# bc95.net
KiCad netlist of a schematic drawn in Altium Designer
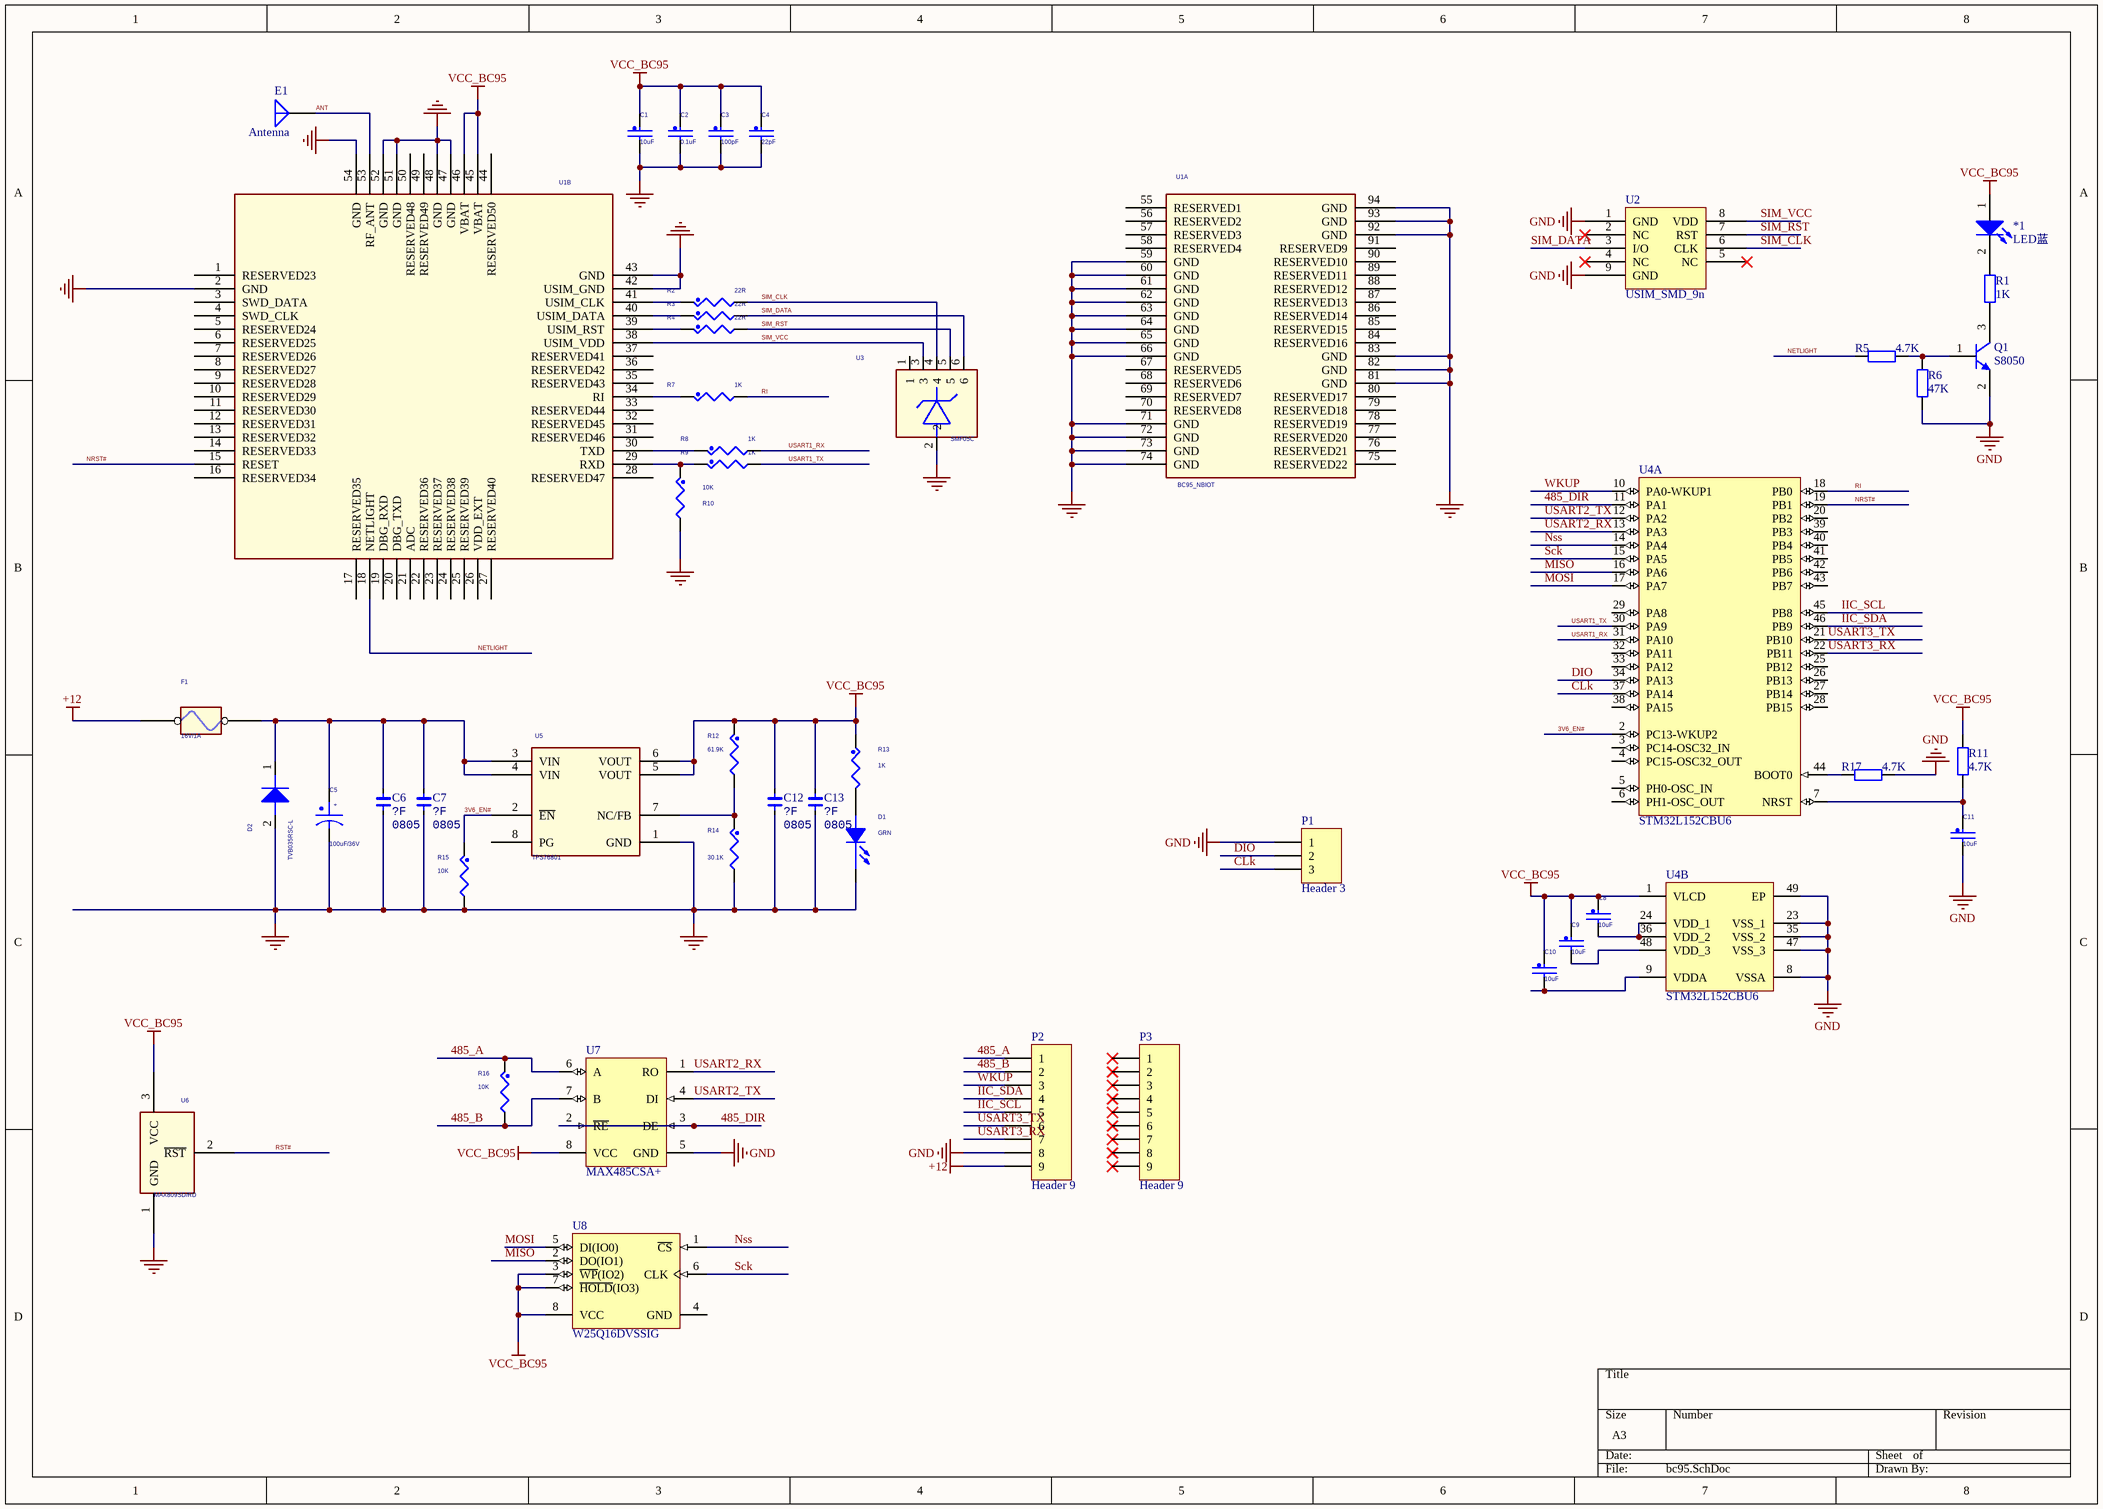
[diagram p0: bc95.SchDoc]

(export (version "E")
  (design (tool "Eeschema 10.0.6"))
  (components
    (comp (ref "*1") (value "LED蓝") (footprint "LED_0603_BLUE") (libsource (lib "du") (part "LED蓝")))
    (comp (ref "C1")
      (value "10uF")
      (footprint "CAP_0603")
      (description "CAP 22uF 1210 25V 10%")
      (fields (field (name "MFG") "Murata") (field (name "MPN") "GRM-RC1210-227K"))
      (libsource (lib "*") (part "CAP_NP"))
    )
    (comp (ref "C2")
      (value "0.1uF")
      (footprint "CAP_0603")
      (description "CAP  0.1uF 0402 25V 10%")
      (fields (field (name "PART NUMBER") "132-000**") (field (name "VOLTAGE") "25V"))
      (libsource (lib "*") (part "CAP_NP"))
    )
    (comp (ref "C3")
      (value "100pF")
      (footprint "CAP_0603")
      (description "CAP  0.1uF 0402 25V 10%")
      (fields (field (name "TOLERANCE") "10%") (field (name "MPN") "GRM-RC0402-104K"))
      (libsource (lib "*") (part "CAP_NP"))
    )
    (comp (ref "C4")
      (value "22pF")
      (footprint "CAP_0603")
      (description "CAP  0.1uF 0402 25V 10%")
      (fields (field (name "PART NUMBER") "132-000**") (field (name "VOLTAGE") "25V"))
      (libsource (lib "*") (part "CAP_NP"))
    )
    (comp (ref "C5")
      (value "100uF/36V")
      (footprint "CAP_TAN_D2917")
      (description "CAP 220UF 1010mm 35V 10%")
      (fields (field (name "MFG") "Murata") (field (name "MPN") "C1210C476K8PAC"))
      (libsource (lib "*") (part "CAP_POL"))
    )
    (comp (ref "C6")
      (value "?F")
      (footprint "PCB_PassiveCap:CAP_0805")
      (description "Capacitor")
      (fields (field (name "TYPE") "0805"))
      (libsource (lib "SCH_Passive") (part "Cap_0805"))
    )
    (comp (ref "C7")
      (value "?F")
      (footprint "PCB_PassiveCap:CAP_0805")
      (description "Capacitor")
      (fields (field (name "TYPE") "0805"))
      (libsource (lib "SCH_Passive") (part "Cap_0805"))
    )
    (comp (ref "C8")
      (value "10uF")
      (footprint "CAP_0603")
      (description "CAP 22uF 1210 25V 10%")
      (fields (field (name "MFG") "Murata") (field (name "MPN") "GRM-RC1210-227K"))
      (libsource (lib "*") (part "CAP_NP"))
    )
    (comp (ref "C9")
      (value "10uF")
      (footprint "CAP_0603")
      (description "CAP 22uF 1210 25V 10%")
      (fields (field (name "MFG") "Murata") (field (name "MPN") "GRM-RC1210-227K"))
      (libsource (lib "*") (part "CAP_NP"))
    )
    (comp (ref "C10")
      (value "10uF")
      (footprint "CAP_0603")
      (description "CAP 22uF 1210 25V 10%")
      (fields (field (name "MFG") "Murata") (field (name "MPN") "GRM-RC1210-227K"))
      (libsource (lib "*") (part "CAP_NP"))
    )
    (comp (ref "C11")
      (value "10uF")
      (footprint "CAP_0603")
      (description "CAP 22uF 1210 25V 10%")
      (fields (field (name "MFG") "Murata") (field (name "MPN") "GRM-RC1210-227K"))
      (libsource (lib "*") (part "CAP_NP"))
    )
    (comp (ref "C12")
      (value "?F")
      (footprint "PCB_PassiveCap:CAP_0805")
      (description "Capacitor")
      (fields (field (name "TYPE") "0805"))
      (libsource (lib "SCH_Passive") (part "Cap_0805"))
    )
    (comp (ref "C13")
      (value "?F")
      (footprint "PCB_PassiveCap:CAP_0805")
      (description "Capacitor")
      (fields (field (name "TYPE") "0805"))
      (libsource (lib "SCH_Passive") (part "Cap_0805"))
    )
    (comp (ref "D1") (value "GRN") (footprint "LED_0603_GREEN") (libsource (lib "*") (part "F5F1")))
    (comp (ref "D2")
      (value "TVB035RSC-L")
      (footprint "IND_1008")
      (description "二极管 浪涌保 dm=35V,Ih=150mA DO-214AA SMB")
      (fields (field (name "MFG") "TYCO"))
      (libsource (lib "*") (part "DIODE"))
    )
    (comp (ref "E1")
      (value "Antenna")
      (footprint "IPX")
      (description "Generic Antenna")
      (fields (field (name "PUBLISHER") "Altium Limited"))
      (libsource (lib "Miscellaneous Devices") (part "Antenna"))
    )
    (comp (ref "F1") (value "16V/1A") (footprint "RES_0805") (libsource (lib "*") (part "FUSEHOLDER")))
    (comp (ref "P1")
      (value "Header 3")
      (footprint "HDR1X3")
      (description "Header, 3-Pin")
      (fields (field (name "PUBLISHER") "Altium Limited"))
      (libsource (lib "Miscellaneous Connectors") (part "Header 3"))
    )
    (comp (ref "P2")
      (value "Header 9")
      (footprint "HDR1X9")
      (description "Header, 9-Pin")
      (fields (field (name "PUBLISHER") "Altium Limited"))
      (libsource (lib "Miscellaneous Connectors") (part "Header 9"))
    )
    (comp (ref "P3")
      (value "Header 9")
      (footprint "HDR1X9")
      (description "Header, 9-Pin")
      (fields (field (name "PUBLISHER") "Altium Limited"))
      (libsource (lib "Miscellaneous Connectors") (part "Header 9"))
    )
    (comp (ref "Q1")
      (value "S8050")
      (footprint "SOT23_M")
      (description "NPN Bipolar Transistor")
      (fields (field (name "PUBLISHER") "Altium Limited"))
      (libsource (lib "Sch_Lib_CommonDrivice") (part "QNPN"))
    )
    (comp (ref "R1")
      (value "1K")
      (footprint "RES_0603")
      (description "Resistor")
      (fields (field (name "PUBLISHER") "Altium Limited"))
      (libsource (lib "") (part "Res_2"))
    )
    (comp (ref "R2")
      (value "22R")
      (footprint "RES_0603")
      (fields
        (field (name "TOLERANCE") "5%")
        (field (name "MFG") "Yageo")
        (field (name "MPN") "RC1206JR-07330R")
      )
      (libsource (lib "*") (part "RES"))
    )
    (comp (ref "R3")
      (value "22R")
      (footprint "RES_0603")
      (fields
        (field (name "MPN") "RC1206JR-07330R")
        (field (name "MFG") "Yageo")
        (field (name "TOLERANCE") "5%")
      )
      (libsource (lib "*") (part "RES"))
    )
    (comp (ref "R4")
      (value "22R")
      (footprint "RES_0603")
      (fields
        (field (name "MPN") "RC1206JR-07330R")
        (field (name "MFG") "Yageo")
        (field (name "TOLERANCE") "5%")
      )
      (libsource (lib "*") (part "RES"))
    )
    (comp (ref "R5")
      (value "4.7K")
      (footprint "RES_0603")
      (description "Resistor")
      (fields (field (name "PUBLISHER") "Altium Limited"))
      (libsource (lib "") (part "Res_1"))
    )
    (comp (ref "R6")
      (value "47K")
      (footprint "RES_0603")
      (description "Resistor")
      (fields (field (name "PUBLISHER") "Altium Limited"))
      (libsource (lib "Sch_Lib_CommonDrivice") (part "Res"))
    )
    (comp (ref "R7")
      (value "1K")
      (footprint "RES_0603")
      (fields
        (field (name "TOLERANCE") "5%")
        (field (name "MFG") "Yageo")
        (field (name "MPN") "RC1206JR-07330R")
      )
      (libsource (lib "*") (part "RES"))
    )
    (comp (ref "R8")
      (value "1K")
      (footprint "RES_0603")
      (fields
        (field (name "MPN") "RC1206JR-07330R")
        (field (name "MFG") "Yageo")
        (field (name "TOLERANCE") "5%")
      )
      (libsource (lib "*") (part "RES"))
    )
    (comp (ref "R9")
      (value "1K")
      (footprint "RES_0603")
      (fields
        (field (name "MPN") "RC1206JR-07330R")
        (field (name "MFG") "Yageo")
        (field (name "TOLERANCE") "5%")
      )
      (libsource (lib "*") (part "RES"))
    )
    (comp (ref "R10")
      (value "10K")
      (footprint "RES_0603")
      (fields
        (field (name "MPN") "RC1206JR-07330R")
        (field (name "MFG") "Yageo")
        (field (name "TOLERANCE") "5%")
      )
      (libsource (lib "*") (part "RES"))
    )
    (comp (ref "R11")
      (value "4.7K")
      (footprint "RES_0603")
      (description "Resistor")
      (fields (field (name "PUBLISHER") "Altium Limited"))
      (libsource (lib "Sch_Lib_CommonDrivice") (part "Res"))
    )
    (comp (ref "R12")
      (value "61.9K")
      (footprint "RES_0603")
      (fields
        (field (name "TOLERANCE") "5%")
        (field (name "MFG") "Yageo")
        (field (name "MPN") "RC1206JR-07330R")
      )
      (libsource (lib "*") (part "RES"))
    )
    (comp (ref "R13")
      (value "1K")
      (footprint "RES_0603")
      (fields (field (name "TOLERANCE") "5%") (field (name "MPN") "RC0402JR-07330R"))
      (libsource (lib "*") (part "RES"))
    )
    (comp (ref "R14")
      (value "30.1K")
      (footprint "RES_0603")
      (fields
        (field (name "MPN") "RC1206JR-07330R")
        (field (name "MFG") "Yageo")
        (field (name "TOLERANCE") "5%")
      )
      (libsource (lib "*") (part "RES"))
    )
    (comp (ref "R15")
      (value "10K")
      (footprint "RES_0603")
      (fields
        (field (name "MPN") "RC1206JR-07330R")
        (field (name "MFG") "Yageo")
        (field (name "TOLERANCE") "5%")
      )
      (libsource (lib "*") (part "RES"))
    )
    (comp (ref "R16")
      (value "10K")
      (footprint "RES_0603")
      (fields
        (field (name "MPN") "RC1206JR-07330R")
        (field (name "MFG") "Yageo")
        (field (name "TOLERANCE") "5%")
      )
      (libsource (lib "*") (part "RES"))
    )
    (comp (ref "R17")
      (value "4.7K")
      (footprint "RES_0603")
      (description "Resistor")
      (fields (field (name "PUBLISHER") "Altium Limited"))
      (libsource (lib "") (part "Res_1"))
    )
    (comp (ref "U1") (value "BC95_NBIOT") (footprint "BC95") (libsource (lib "*") (part "BC95_NBIOT_4")))
    (comp (ref "U2")
      (value "USIM_SMD_9n")
      (footprint "SON127P600X75_HS-9N")
      (libsource (lib "du") (part "USIM_SMD_9n"))
    )
    (comp (ref "U3") (value "SMF05C") (footprint "SOT65P210X100-6N") (libsource (lib "*") (part "SMF05C_0")))
    (comp (ref "U4")
      (value "STM32L152CBU6")
      (footprint "STM-UFQFPN48_M")
      (libsource (lib "Altium Content Vault") (part "MC-ARM-STM32L15XX6_8_B-SQ49"))
    )
    (comp (ref "U5") (value "TPS76801") (footprint "SO8_M") (libsource (lib "*") (part "TPS768XX_1")))
    (comp (ref "U6") (value "MAX809SD/RD") (footprint "SOT23_M") (libsource (lib "*") (part "MAX809SD/RD")))
    (comp (ref "U7")
      (value "MAX485CSA+")
      (footprint "MAXM-MAX485CSA+-8_M")
      (fields (field (name "MANUFACTURER") "Maxim"))
      (libsource (lib "Altium Content Vault") (part "MAXM-MAX485CSA+-8"))
    )
    (comp (ref "U8")
      (value "W25Q16DVSSIG")
      (footprint "WINB-W25Q16DVSSIG-8_M")
      (description "IC FLASH 16MBIT 104MHZ 8SOIC")
      (fields (field (name "MANUFACTURER") "Winbond"))
      (libsource (lib "Altium Content Vault") (part "WINB-W25Q16DVSSIG-8"))
    )
  )
  (nets
    (net (code "1") (name "+12") (class "Default")
      (node (ref "F1") (pin "1") (pinfunction "1_1") (pintype "passive"))
      (node (ref "P2") (pin "9") (pinfunction "9_9") (pintype "passive"))
    )
    (net (code "2") (name "/3V6_EN#") (class "Default")
      (node (ref "R15") (pin "1") (pinfunction "1_1") (pintype "passive"))
      (node (ref "U4") (pin "2") (pinfunction "PC13-WKUP2_2") (pintype "bidirectional"))
      (node (ref "U5") (pin "2") (pinfunction "~{EN}_2") (pintype "passive"))
    )
    (net (code "3") (name "/485_A") (class "Default")
      (node (ref "P2") (pin "1") (pinfunction "1_1") (pintype "passive"))
      (node (ref "R16") (pin "1") (pinfunction "1_1") (pintype "passive"))
      (node (ref "U7") (pin "6") (pinfunction "A_6") (pintype "bidirectional"))
    )
    (net (code "4") (name "/485_B") (class "Default")
      (node (ref "P2") (pin "2") (pinfunction "2_2") (pintype "passive"))
      (node (ref "R16") (pin "2") (pinfunction "2_2") (pintype "passive"))
      (node (ref "U7") (pin "7") (pinfunction "B_7") (pintype "bidirectional"))
    )
    (net (code "5") (name "/485_DIR") (class "Default")
      (node (ref "U4") (pin "11") (pinfunction "PA1_11") (pintype "bidirectional"))
      (node (ref "U7") (pin "2") (pinfunction "~{RE}_2") (pintype "input"))
      (node (ref "U7") (pin "3") (pinfunction "DE_3") (pintype "input"))
    )
    (net (code "6") (name "/ANT") (class "Default")
      (node (ref "E1") (pin "1") (pinfunction "A_1") (pintype "passive"))
      (node (ref "U1") (pin "53") (pinfunction "RF_ANT_53") (pintype "passive"))
    )
    (net (code "7") (name "/CLk") (class "Default")
      (node (ref "P1") (pin "3") (pinfunction "3_3") (pintype "passive"))
      (node (ref "U4") (pin "37") (pinfunction "PA14_37") (pintype "bidirectional"))
    )
    (net (code "8") (name "/DIO") (class "Default")
      (node (ref "P1") (pin "2") (pinfunction "2_2") (pintype "passive"))
      (node (ref "U4") (pin "34") (pinfunction "PA13_34") (pintype "bidirectional"))
    )
    (net (code "9") (name "/IIC_SCL") (class "Default")
      (node (ref "P2") (pin "5") (pinfunction "5_5") (pintype "passive"))
      (node (ref "U4") (pin "45") (pinfunction "PB8_45") (pintype "bidirectional"))
    )
    (net (code "10") (name "/IIC_SDA") (class "Default")
      (node (ref "P2") (pin "4") (pinfunction "4_4") (pintype "passive"))
      (node (ref "U4") (pin "46") (pinfunction "PB9_46") (pintype "bidirectional"))
    )
    (net (code "11") (name "/MISO") (class "Default")
      (node (ref "U4") (pin "16") (pinfunction "PA6_16") (pintype "bidirectional"))
      (node (ref "U8") (pin "2") (pinfunction "DO(IO1)_2") (pintype "bidirectional"))
    )
    (net (code "12") (name "/MOSI") (class "Default")
      (node (ref "U4") (pin "17") (pinfunction "PA7_17") (pintype "bidirectional"))
      (node (ref "U8") (pin "5") (pinfunction "DI(IO0)_5") (pintype "bidirectional"))
    )
    (net (code "13") (name "/NETLIGHT") (class "Default")
      (node (ref "R5") (pin "2") (pinfunction "2_2") (pintype "passive"))
      (node (ref "U1") (pin "18") (pinfunction "NETLIGHT_18") (pintype "passive"))
    )
    (net (code "14") (name "/NRST#") (class "Default")
      (node (ref "U1") (pin "15") (pinfunction "RESET_15") (pintype "passive"))
      (node (ref "U4") (pin "19") (pinfunction "PB1_19") (pintype "bidirectional"))
    )
    (net (code "15") (name "/Nss") (class "Default")
      (node (ref "U4") (pin "14") (pinfunction "PA4_14") (pintype "bidirectional"))
      (node (ref "U8") (pin "1") (pinfunction "~{CS}_1") (pintype "input"))
    )
    (net (code "16") (name "/RI") (class "Default")
      (node (ref "R7") (pin "2") (pinfunction "2_2") (pintype "passive"))
      (node (ref "U4") (pin "18") (pinfunction "PB0_18") (pintype "bidirectional"))
    )
    (net (code "17") (name "/RST#") (class "Default")
      (node (ref "U6") (pin "2") (pinfunction "~{RST}_2") (pintype "passive"))
    )
    (net (code "18") (name "/SIM_CLK") (class "Default")
      (node (ref "R2") (pin "2") (pinfunction "2_2") (pintype "passive"))
      (node (ref "U2") (pin "6") (pinfunction "CLK_6") (pintype "passive"))
      (node (ref "U3") (pin "4") (pinfunction "4_4") (pintype "passive"))
    )
    (net (code "19") (name "/SIM_DATA") (class "Default")
      (node (ref "R3") (pin "2") (pinfunction "2_2") (pintype "passive"))
      (node (ref "U2") (pin "3") (pinfunction "I/O_3") (pintype "passive"))
      (node (ref "U3") (pin "6") (pinfunction "6_6") (pintype "passive"))
    )
    (net (code "20") (name "/SIM_RST") (class "Default")
      (node (ref "R4") (pin "2") (pinfunction "2_2") (pintype "passive"))
      (node (ref "U2") (pin "7") (pinfunction "RST_7") (pintype "passive"))
      (node (ref "U3") (pin "5") (pinfunction "5_5") (pintype "passive"))
    )
    (net (code "21") (name "/SIM_VCC") (class "Default")
      (node (ref "U1") (pin "38") (pinfunction "USIM_VDD_38") (pintype "passive"))
      (node (ref "U2") (pin "8") (pinfunction "VDD_8") (pintype "passive"))
      (node (ref "U3") (pin "3") (pinfunction "3_3") (pintype "passive"))
    )
    (net (code "22") (name "/Sck") (class "Default")
      (node (ref "U4") (pin "15") (pinfunction "PA5_15") (pintype "bidirectional"))
      (node (ref "U8") (pin "6") (pinfunction "CLK_6") (pintype "input"))
    )
    (net (code "23") (name "/USART1_RX") (class "Default")
      (node (ref "R8") (pin "2") (pinfunction "2_2") (pintype "passive"))
      (node (ref "U4") (pin "31") (pinfunction "PA10_31") (pintype "bidirectional"))
    )
    (net (code "24") (name "/USART1_TX") (class "Default")
      (node (ref "R9") (pin "2") (pinfunction "2_2") (pintype "passive"))
      (node (ref "U4") (pin "30") (pinfunction "PA9_30") (pintype "bidirectional"))
    )
    (net (code "25") (name "/USART2_RX") (class "Default")
      (node (ref "U4") (pin "13") (pinfunction "PA3_13") (pintype "bidirectional"))
      (node (ref "U7") (pin "1") (pinfunction "RO_1") (pintype "tri_state"))
    )
    (net (code "26") (name "/USART2_TX") (class "Default")
      (node (ref "U4") (pin "12") (pinfunction "PA2_12") (pintype "bidirectional"))
      (node (ref "U7") (pin "4") (pinfunction "DI_4") (pintype "input"))
    )
    (net (code "27") (name "/USART3_RX") (class "Default")
      (node (ref "P2") (pin "7") (pinfunction "7_7") (pintype "passive"))
      (node (ref "U4") (pin "22") (pinfunction "PB11_22") (pintype "bidirectional"))
    )
    (net (code "28") (name "/USART3_TX") (class "Default")
      (node (ref "P2") (pin "6") (pinfunction "6_6") (pintype "passive"))
      (node (ref "U4") (pin "21") (pinfunction "PB10_21") (pintype "bidirectional"))
    )
    (net (code "29") (name "/WKUP") (class "Default")
      (node (ref "P2") (pin "3") (pinfunction "3_3") (pintype "passive"))
      (node (ref "U4") (pin "10") (pinfunction "PA0-WKUP1_10") (pintype "bidirectional"))
    )
    (net (code "30") (name "GND") (class "Default")
      (node (ref "C1") (pin "2") (pinfunction "2_2") (pintype "passive"))
      (node (ref "C11") (pin "2") (pinfunction "2_2") (pintype "passive"))
      (node (ref "C12") (pin "1") (pinfunction "1_1") (pintype "passive"))
      (node (ref "C13") (pin "1") (pinfunction "1_1") (pintype "passive"))
      (node (ref "C2") (pin "2") (pinfunction "2_2") (pintype "passive"))
      (node (ref "C3") (pin "2") (pinfunction "2_2") (pintype "passive"))
      (node (ref "C4") (pin "2") (pinfunction "2_2") (pintype "passive"))
      (node (ref "C5") (pin "2") (pinfunction "2_2") (pintype "passive"))
      (node (ref "C6") (pin "1") (pinfunction "1_1") (pintype "passive"))
      (node (ref "C7") (pin "1") (pinfunction "1_1") (pintype "passive"))
      (node (ref "D1") (pin "1") (pinfunction "CATHODE_1") (pintype "passive"))
      (node (ref "D2") (pin "2") (pinfunction "ANODE_2") (pintype "passive"))
      (node (ref "P1") (pin "1") (pinfunction "1_1") (pintype "passive"))
      (node (ref "P2") (pin "8") (pinfunction "8_8") (pintype "passive"))
      (node (ref "Q1") (pin "2") (pinfunction "E_2") (pintype "passive"))
      (node (ref "R10") (pin "2") (pinfunction "2_2") (pintype "passive"))
      (node (ref "R14") (pin "2") (pinfunction "2_2") (pintype "passive"))
      (node (ref "R15") (pin "2") (pinfunction "2_2") (pintype "passive"))
      (node (ref "R17") (pin "1") (pinfunction "1_1") (pintype "passive"))
      (node (ref "R6") (pin "2") (pinfunction "2_2") (pintype "passive"))
      (node (ref "U1") (pin "2") (pinfunction "GND_2") (pintype "power_in"))
      (node (ref "U1") (pin "42") (pinfunction "USIM_GND_42") (pintype "passive"))
      (node (ref "U1") (pin "43") (pinfunction "GND_43") (pintype "power_in"))
      (node (ref "U1") (pin "47") (pinfunction "GND_47") (pintype "power_in"))
      (node (ref "U1") (pin "48") (pinfunction "GND_48") (pintype "power_in"))
      (node (ref "U1") (pin "51") (pinfunction "GND_51") (pintype "power_in"))
      (node (ref "U1") (pin "52") (pinfunction "GND_52") (pintype "power_in"))
      (node (ref "U1") (pin "54") (pinfunction "GND_54") (pintype "power_in"))
      (node (ref "U1") (pin "59") (pinfunction "GND_59") (pintype "power_in"))
      (node (ref "U1") (pin "60") (pinfunction "GND_60") (pintype "power_in"))
      (node (ref "U1") (pin "61") (pinfunction "GND_61") (pintype "power_in"))
      (node (ref "U1") (pin "62") (pinfunction "GND_62") (pintype "power_in"))
      (node (ref "U1") (pin "63") (pinfunction "GND_63") (pintype "power_in"))
      (node (ref "U1") (pin "64") (pinfunction "GND_64") (pintype "power_in"))
      (node (ref "U1") (pin "65") (pinfunction "GND_65") (pintype "power_in"))
      (node (ref "U1") (pin "66") (pinfunction "GND_66") (pintype "power_in"))
      (node (ref "U1") (pin "71") (pinfunction "GND_71") (pintype "power_in"))
      (node (ref "U1") (pin "72") (pinfunction "GND_72") (pintype "power_in"))
      (node (ref "U1") (pin "73") (pinfunction "GND_73") (pintype "power_in"))
      (node (ref "U1") (pin "74") (pinfunction "GND_74") (pintype "power_in"))
      (node (ref "U1") (pin "81") (pinfunction "GND_81") (pintype "power_in"))
      (node (ref "U1") (pin "82") (pinfunction "GND_82") (pintype "power_in"))
      (node (ref "U1") (pin "83") (pinfunction "GND_83") (pintype "power_in"))
      (node (ref "U1") (pin "92") (pinfunction "GND_92") (pintype "power_in"))
      (node (ref "U1") (pin "93") (pinfunction "GND_93") (pintype "power_in"))
      (node (ref "U1") (pin "94") (pinfunction "GND_94") (pintype "power_in"))
      (node (ref "U2") (pin "1") (pinfunction "GND_1") (pintype "passive"))
      (node (ref "U2") (pin "9") (pinfunction "GND_9") (pintype "passive"))
      (node (ref "U3") (pin "2") (pinfunction "2_2") (pintype "passive"))
      (node (ref "U4") (pin "23") (pinfunction "VSS_1_23") (pintype "power_in"))
      (node (ref "U4") (pin "35") (pinfunction "VSS_2_35") (pintype "power_in"))
      (node (ref "U4") (pin "47") (pinfunction "VSS_3_47") (pintype "power_in"))
      (node (ref "U4") (pin "49") (pinfunction "EP_49") (pintype "power_in"))
      (node (ref "U4") (pin "8") (pinfunction "VSSA_8") (pintype "power_in"))
      (node (ref "U5") (pin "1") (pinfunction "GND_1") (pintype "power_in"))
      (node (ref "U6") (pin "1") (pinfunction "GND_1") (pintype "passive"))
      (node (ref "U7") (pin "5") (pinfunction "GND_5") (pintype "power_in"))
    )
    (net (code "31") (name "Net-(*1-Pad2)") (class "Default")
      (node (ref "*1") (pin "2") (pinfunction "2_2") (pintype "passive"))
      (node (ref "R1") (pin "2") (pinfunction "2_2") (pintype "passive"))
    )
    (net (code "32") (name "Net-(D1-ANODE)") (class "Default")
      (node (ref "D1") (pin "2") (pinfunction "ANODE_2") (pintype "passive"))
      (node (ref "R13") (pin "2") (pinfunction "2_2") (pintype "passive"))
    )
    (net (code "33") (name "Net-(D2-CATHODE)") (class "Default")
      (node (ref "C5") (pin "1") (pinfunction "1_1") (pintype "passive"))
      (node (ref "C6") (pin "2") (pinfunction "2_2") (pintype "passive"))
      (node (ref "C7") (pin "2") (pinfunction "2_2") (pintype "passive"))
      (node (ref "D2") (pin "1") (pinfunction "CATHODE_1") (pintype "passive"))
      (node (ref "F1") (pin "2") (pinfunction "2_2") (pintype "passive"))
      (node (ref "U5") (pin "3") (pinfunction "VIN_3") (pintype "power_in"))
      (node (ref "U5") (pin "4") (pinfunction "VIN_4") (pintype "power_in"))
    )
    (net (code "34") (name "Net-(Q1-B)") (class "Default")
      (node (ref "Q1") (pin "1") (pinfunction "B_1") (pintype "passive"))
      (node (ref "R5") (pin "1") (pinfunction "1_1") (pintype "passive"))
      (node (ref "R6") (pin "1") (pinfunction "1_1") (pintype "passive"))
    )
    (net (code "35") (name "Net-(Q1-C)") (class "Default")
      (node (ref "Q1") (pin "3") (pinfunction "C_3") (pintype "passive"))
      (node (ref "R1") (pin "1") (pinfunction "1_1") (pintype "passive"))
    )
    (net (code "36") (name "Net-(U1B-RI)") (class "Default")
      (node (ref "R7") (pin "1") (pinfunction "1_1") (pintype "passive"))
      (node (ref "U1") (pin "34") (pinfunction "RI_34") (pintype "passive"))
    )
    (net (code "37") (name "Net-(U1B-RXD)") (class "Default")
      (node (ref "R10") (pin "1") (pinfunction "1_1") (pintype "passive"))
      (node (ref "R9") (pin "1") (pinfunction "1_1") (pintype "passive"))
      (node (ref "U1") (pin "29") (pinfunction "RXD_29") (pintype "passive"))
    )
    (net (code "38") (name "Net-(U1B-TXD)") (class "Default")
      (node (ref "R8") (pin "1") (pinfunction "1_1") (pintype "passive"))
      (node (ref "U1") (pin "30") (pinfunction "TXD_30") (pintype "passive"))
    )
    (net (code "39") (name "Net-(U1B-USIM_CLK)") (class "Default")
      (node (ref "R2") (pin "1") (pinfunction "1_1") (pintype "passive"))
      (node (ref "U1") (pin "41") (pinfunction "USIM_CLK_41") (pintype "passive"))
    )
    (net (code "40") (name "Net-(U1B-USIM_DATA)") (class "Default")
      (node (ref "R3") (pin "1") (pinfunction "1_1") (pintype "passive"))
      (node (ref "U1") (pin "40") (pinfunction "USIM_DATA_40") (pintype "passive"))
    )
    (net (code "41") (name "Net-(U1B-USIM_RST)") (class "Default")
      (node (ref "R4") (pin "1") (pinfunction "1_1") (pintype "passive"))
      (node (ref "U1") (pin "39") (pinfunction "USIM_RST_39") (pintype "passive"))
    )
    (net (code "42") (name "Net-(U4A-BOOT0)") (class "Default")
      (node (ref "R17") (pin "2") (pinfunction "2_2") (pintype "passive"))
      (node (ref "U4") (pin "44") (pinfunction "BOOT0_44") (pintype "input"))
    )
    (net (code "43") (name "Net-(U4A-NRST)") (class "Default")
      (node (ref "C11") (pin "1") (pinfunction "1_1") (pintype "passive"))
      (node (ref "R11") (pin "2") (pinfunction "2_2") (pintype "passive"))
      (node (ref "U4") (pin "7") (pinfunction "NRST_7") (pintype "bidirectional"))
    )
    (net (code "44") (name "Net-(U4B-VDDA)") (class "Default")
      (node (ref "C10") (pin "2") (pinfunction "2_2") (pintype "passive"))
      (node (ref "U4") (pin "9") (pinfunction "VDDA_9") (pintype "power_in"))
    )
    (net (code "45") (name "Net-(U4B-VDD_1)") (class "Default")
      (node (ref "C8") (pin "2") (pinfunction "2_2") (pintype "passive"))
      (node (ref "U4") (pin "24") (pinfunction "VDD_1_24") (pintype "power_in"))
      (node (ref "U4") (pin "36") (pinfunction "VDD_2_36") (pintype "power_in"))
    )
    (net (code "46") (name "Net-(U4B-VDD_3)") (class "Default")
      (node (ref "C9") (pin "2") (pinfunction "2_2") (pintype "passive"))
      (node (ref "U4") (pin "48") (pinfunction "VDD_3_48") (pintype "power_in"))
    )
    (net (code "47") (name "Net-(U5-NC{slash}FB)") (class "Default")
      (node (ref "R12") (pin "2") (pinfunction "2_2") (pintype "passive"))
      (node (ref "R14") (pin "1") (pinfunction "1_1") (pintype "passive"))
      (node (ref "U5") (pin "7") (pinfunction "NC/FB_7") (pintype "passive"))
    )
    (net (code "48") (name "VCC_BC95") (class "Default")
      (node (ref "*1") (pin "1") (pinfunction "1_1") (pintype "passive"))
      (node (ref "C1") (pin "1") (pinfunction "1_1") (pintype "passive"))
      (node (ref "C10") (pin "1") (pinfunction "1_1") (pintype "passive"))
      (node (ref "C12") (pin "2") (pinfunction "2_2") (pintype "passive"))
      (node (ref "C13") (pin "2") (pinfunction "2_2") (pintype "passive"))
      (node (ref "C2") (pin "1") (pinfunction "1_1") (pintype "passive"))
      (node (ref "C3") (pin "1") (pinfunction "1_1") (pintype "passive"))
      (node (ref "C4") (pin "1") (pinfunction "1_1") (pintype "passive"))
      (node (ref "C8") (pin "1") (pinfunction "1_1") (pintype "passive"))
      (node (ref "C9") (pin "1") (pinfunction "1_1") (pintype "passive"))
      (node (ref "R11") (pin "1") (pinfunction "1_1") (pintype "passive"))
      (node (ref "R12") (pin "1") (pinfunction "1_1") (pintype "passive"))
      (node (ref "R13") (pin "1") (pinfunction "1_1") (pintype "passive"))
      (node (ref "U1") (pin "45") (pinfunction "VBAT_45") (pintype "power_in"))
      (node (ref "U1") (pin "46") (pinfunction "VBAT_46") (pintype "power_in"))
      (node (ref "U4") (pin "1") (pinfunction "VLCD_1") (pintype "power_in"))
      (node (ref "U5") (pin "5") (pinfunction "VOUT_5") (pintype "power_in"))
      (node (ref "U5") (pin "6") (pinfunction "VOUT_6") (pintype "power_in"))
      (node (ref "U6") (pin "3") (pinfunction "VCC_3") (pintype "passive"))
      (node (ref "U7") (pin "8") (pinfunction "VCC_8") (pintype "power_in"))
      (node (ref "U8") (pin "3") (pinfunction "~{WP}(IO2)_3") (pintype "bidirectional"))
      (node (ref "U8") (pin "7") (pinfunction "~{HOLD}(IO3)_7") (pintype "bidirectional"))
      (node (ref "U8") (pin "8") (pinfunction "VCC_8") (pintype "power_in"))
    )
    (net (code "49") (name "unconnected-(P3-Pad1)") (class "Default")
      (node (ref "P3") (pin "1") (pinfunction "1_1") (pintype "passive+no_connect"))
    )
    (net (code "50") (name "unconnected-(P3-Pad2)") (class "Default")
      (node (ref "P3") (pin "2") (pinfunction "2_2") (pintype "passive+no_connect"))
    )
    (net (code "51") (name "unconnected-(P3-Pad3)") (class "Default")
      (node (ref "P3") (pin "3") (pinfunction "3_3") (pintype "passive+no_connect"))
    )
    (net (code "52") (name "unconnected-(P3-Pad4)") (class "Default")
      (node (ref "P3") (pin "4") (pinfunction "4_4") (pintype "passive+no_connect"))
    )
    (net (code "53") (name "unconnected-(P3-Pad5)") (class "Default")
      (node (ref "P3") (pin "5") (pinfunction "5_5") (pintype "passive+no_connect"))
    )
    (net (code "54") (name "unconnected-(P3-Pad6)") (class "Default")
      (node (ref "P3") (pin "6") (pinfunction "6_6") (pintype "passive+no_connect"))
    )
    (net (code "55") (name "unconnected-(P3-Pad7)") (class "Default")
      (node (ref "P3") (pin "7") (pinfunction "7_7") (pintype "passive+no_connect"))
    )
    (net (code "56") (name "unconnected-(P3-Pad8)") (class "Default")
      (node (ref "P3") (pin "8") (pinfunction "8_8") (pintype "passive+no_connect"))
    )
    (net (code "57") (name "unconnected-(P3-Pad9)") (class "Default")
      (node (ref "P3") (pin "9") (pinfunction "9_9") (pintype "passive+no_connect"))
    )
    (net (code "58") (name "unconnected-(U1A-RESERVED1-Pad55)") (class "Default")
      (node (ref "U1") (pin "55") (pinfunction "RESERVED1_55") (pintype "passive"))
    )
    (net (code "59") (name "unconnected-(U1A-RESERVED2-Pad56)") (class "Default")
      (node (ref "U1") (pin "56") (pinfunction "RESERVED2_56") (pintype "passive"))
    )
    (net (code "60") (name "unconnected-(U1A-RESERVED3-Pad57)") (class "Default")
      (node (ref "U1") (pin "57") (pinfunction "RESERVED3_57") (pintype "passive"))
    )
    (net (code "61") (name "unconnected-(U1A-RESERVED4-Pad58)") (class "Default")
      (node (ref "U1") (pin "58") (pinfunction "RESERVED4_58") (pintype "passive"))
    )
    (net (code "62") (name "unconnected-(U1A-RESERVED5-Pad67)") (class "Default")
      (node (ref "U1") (pin "67") (pinfunction "RESERVED5_67") (pintype "passive"))
    )
    (net (code "63") (name "unconnected-(U1A-RESERVED6-Pad68)") (class "Default")
      (node (ref "U1") (pin "68") (pinfunction "RESERVED6_68") (pintype "passive"))
    )
    (net (code "64") (name "unconnected-(U1A-RESERVED7-Pad69)") (class "Default")
      (node (ref "U1") (pin "69") (pinfunction "RESERVED7_69") (pintype "passive"))
    )
    (net (code "65") (name "unconnected-(U1A-RESERVED8-Pad70)") (class "Default")
      (node (ref "U1") (pin "70") (pinfunction "RESERVED8_70") (pintype "passive"))
    )
    (net (code "66") (name "unconnected-(U1A-RESERVED9-Pad91)") (class "Default")
      (node (ref "U1") (pin "91") (pinfunction "RESERVED9_91") (pintype "passive"))
    )
    (net (code "67") (name "unconnected-(U1A-RESERVED10-Pad90)") (class "Default")
      (node (ref "U1") (pin "90") (pinfunction "RESERVED10_90") (pintype "passive"))
    )
    (net (code "68") (name "unconnected-(U1A-RESERVED11-Pad89)") (class "Default")
      (node (ref "U1") (pin "89") (pinfunction "RESERVED11_89") (pintype "passive"))
    )
    (net (code "69") (name "unconnected-(U1A-RESERVED12-Pad88)") (class "Default")
      (node (ref "U1") (pin "88") (pinfunction "RESERVED12_88") (pintype "passive"))
    )
    (net (code "70") (name "unconnected-(U1A-RESERVED13-Pad87)") (class "Default")
      (node (ref "U1") (pin "87") (pinfunction "RESERVED13_87") (pintype "passive"))
    )
    (net (code "71") (name "unconnected-(U1A-RESERVED14-Pad86)") (class "Default")
      (node (ref "U1") (pin "86") (pinfunction "RESERVED14_86") (pintype "passive"))
    )
    (net (code "72") (name "unconnected-(U1A-RESERVED15-Pad85)") (class "Default")
      (node (ref "U1") (pin "85") (pinfunction "RESERVED15_85") (pintype "passive"))
    )
    (net (code "73") (name "unconnected-(U1A-RESERVED16-Pad84)") (class "Default")
      (node (ref "U1") (pin "84") (pinfunction "RESERVED16_84") (pintype "passive"))
    )
    (net (code "74") (name "unconnected-(U1A-RESERVED17-Pad80)") (class "Default")
      (node (ref "U1") (pin "80") (pinfunction "RESERVED17_80") (pintype "passive"))
    )
    (net (code "75") (name "unconnected-(U1A-RESERVED18-Pad79)") (class "Default")
      (node (ref "U1") (pin "79") (pinfunction "RESERVED18_79") (pintype "passive"))
    )
    (net (code "76") (name "unconnected-(U1A-RESERVED19-Pad78)") (class "Default")
      (node (ref "U1") (pin "78") (pinfunction "RESERVED19_78") (pintype "passive"))
    )
    (net (code "77") (name "unconnected-(U1A-RESERVED20-Pad77)") (class "Default")
      (node (ref "U1") (pin "77") (pinfunction "RESERVED20_77") (pintype "passive"))
    )
    (net (code "78") (name "unconnected-(U1A-RESERVED21-Pad76)") (class "Default")
      (node (ref "U1") (pin "76") (pinfunction "RESERVED21_76") (pintype "passive"))
    )
    (net (code "79") (name "unconnected-(U1A-RESERVED22-Pad75)") (class "Default")
      (node (ref "U1") (pin "75") (pinfunction "RESERVED22_75") (pintype "passive"))
    )
    (net (code "80") (name "unconnected-(U1B-ADC-Pad21)") (class "Default")
      (node (ref "U1") (pin "21") (pinfunction "ADC_21") (pintype "passive"))
    )
    (net (code "81") (name "unconnected-(U1B-DBG_RXD-Pad19)") (class "Default")
      (node (ref "U1") (pin "19") (pinfunction "DBG_RXD_19") (pintype "passive"))
    )
    (net (code "82") (name "unconnected-(U1B-DBG_TXD-Pad20)") (class "Default")
      (node (ref "U1") (pin "20") (pinfunction "DBG_TXD_20") (pintype "passive"))
    )
    (net (code "83") (name "unconnected-(U1B-RESERVED23-Pad1)") (class "Default")
      (node (ref "U1") (pin "1") (pinfunction "RESERVED23_1") (pintype "passive"))
    )
    (net (code "84") (name "unconnected-(U1B-RESERVED24-Pad5)") (class "Default")
      (node (ref "U1") (pin "5") (pinfunction "RESERVED24_5") (pintype "passive"))
    )
    (net (code "85") (name "unconnected-(U1B-RESERVED25-Pad6)") (class "Default")
      (node (ref "U1") (pin "6") (pinfunction "RESERVED25_6") (pintype "passive"))
    )
    (net (code "86") (name "unconnected-(U1B-RESERVED26-Pad7)") (class "Default")
      (node (ref "U1") (pin "7") (pinfunction "RESERVED26_7") (pintype "passive"))
    )
    (net (code "87") (name "unconnected-(U1B-RESERVED27-Pad8)") (class "Default")
      (node (ref "U1") (pin "8") (pinfunction "RESERVED27_8") (pintype "passive"))
    )
    (net (code "88") (name "unconnected-(U1B-RESERVED28-Pad9)") (class "Default")
      (node (ref "U1") (pin "9") (pinfunction "RESERVED28_9") (pintype "passive"))
    )
    (net (code "89") (name "unconnected-(U1B-RESERVED29-Pad10)") (class "Default")
      (node (ref "U1") (pin "10") (pinfunction "RESERVED29_10") (pintype "passive"))
    )
    (net (code "90") (name "unconnected-(U1B-RESERVED30-Pad11)") (class "Default")
      (node (ref "U1") (pin "11") (pinfunction "RESERVED30_11") (pintype "passive"))
    )
    (net (code "91") (name "unconnected-(U1B-RESERVED31-Pad12)") (class "Default")
      (node (ref "U1") (pin "12") (pinfunction "RESERVED31_12") (pintype "passive"))
    )
    (net (code "92") (name "unconnected-(U1B-RESERVED32-Pad13)") (class "Default")
      (node (ref "U1") (pin "13") (pinfunction "RESERVED32_13") (pintype "passive"))
    )
    (net (code "93") (name "unconnected-(U1B-RESERVED33-Pad14)") (class "Default")
      (node (ref "U1") (pin "14") (pinfunction "RESERVED33_14") (pintype "passive"))
    )
    (net (code "94") (name "unconnected-(U1B-RESERVED34-Pad16)") (class "Default")
      (node (ref "U1") (pin "16") (pinfunction "RESERVED34_16") (pintype "passive"))
    )
    (net (code "95") (name "unconnected-(U1B-RESERVED35-Pad17)") (class "Default")
      (node (ref "U1") (pin "17") (pinfunction "RESERVED35_17") (pintype "passive"))
    )
    (net (code "96") (name "unconnected-(U1B-RESERVED36-Pad22)") (class "Default")
      (node (ref "U1") (pin "22") (pinfunction "RESERVED36_22") (pintype "passive"))
    )
    (net (code "97") (name "unconnected-(U1B-RESERVED37-Pad23)") (class "Default")
      (node (ref "U1") (pin "23") (pinfunction "RESERVED37_23") (pintype "passive"))
    )
    (net (code "98") (name "unconnected-(U1B-RESERVED38-Pad24)") (class "Default")
      (node (ref "U1") (pin "24") (pinfunction "RESERVED38_24") (pintype "passive"))
    )
    (net (code "99") (name "unconnected-(U1B-RESERVED39-Pad25)") (class "Default")
      (node (ref "U1") (pin "25") (pinfunction "RESERVED39_25") (pintype "passive"))
    )
    (net (code "100") (name "unconnected-(U1B-RESERVED40-Pad27)") (class "Default")
      (node (ref "U1") (pin "27") (pinfunction "RESERVED40_27") (pintype "passive"))
    )
    (net (code "101") (name "unconnected-(U1B-RESERVED41-Pad37)") (class "Default")
      (node (ref "U1") (pin "37") (pinfunction "RESERVED41_37") (pintype "passive"))
    )
    (net (code "102") (name "unconnected-(U1B-RESERVED42-Pad36)") (class "Default")
      (node (ref "U1") (pin "36") (pinfunction "RESERVED42_36") (pintype "passive"))
    )
    (net (code "103") (name "unconnected-(U1B-RESERVED43-Pad35)") (class "Default")
      (node (ref "U1") (pin "35") (pinfunction "RESERVED43_35") (pintype "passive"))
    )
    (net (code "104") (name "unconnected-(U1B-RESERVED44-Pad33)") (class "Default")
      (node (ref "U1") (pin "33") (pinfunction "RESERVED44_33") (pintype "passive"))
    )
    (net (code "105") (name "unconnected-(U1B-RESERVED45-Pad32)") (class "Default")
      (node (ref "U1") (pin "32") (pinfunction "RESERVED45_32") (pintype "passive"))
    )
    (net (code "106") (name "unconnected-(U1B-RESERVED46-Pad31)") (class "Default")
      (node (ref "U1") (pin "31") (pinfunction "RESERVED46_31") (pintype "passive"))
    )
    (net (code "107") (name "unconnected-(U1B-RESERVED47-Pad28)") (class "Default")
      (node (ref "U1") (pin "28") (pinfunction "RESERVED47_28") (pintype "passive"))
    )
    (net (code "108") (name "unconnected-(U1B-RESERVED48-Pad50)") (class "Default")
      (node (ref "U1") (pin "50") (pinfunction "RESERVED48_50") (pintype "passive"))
    )
    (net (code "109") (name "unconnected-(U1B-RESERVED49-Pad49)") (class "Default")
      (node (ref "U1") (pin "49") (pinfunction "RESERVED49_49") (pintype "passive"))
    )
    (net (code "110") (name "unconnected-(U1B-RESERVED50-Pad44)") (class "Default")
      (node (ref "U1") (pin "44") (pinfunction "RESERVED50_44") (pintype "passive"))
    )
    (net (code "111") (name "unconnected-(U1B-SWD_CLK-Pad4)") (class "Default")
      (node (ref "U1") (pin "4") (pinfunction "SWD_CLK_4") (pintype "passive"))
    )
    (net (code "112") (name "unconnected-(U1B-SWD_DATA-Pad3)") (class "Default")
      (node (ref "U1") (pin "3") (pinfunction "SWD_DATA_3") (pintype "passive"))
    )
    (net (code "113") (name "unconnected-(U1B-VDD_EXT-Pad26)") (class "Default")
      (node (ref "U1") (pin "26") (pinfunction "VDD_EXT_26") (pintype "passive"))
    )
    (net (code "114") (name "unconnected-(U2-NC-Pad2)") (class "Default")
      (node (ref "U2") (pin "2") (pinfunction "NC_2") (pintype "passive+no_connect"))
    )
    (net (code "115") (name "unconnected-(U2-NC-Pad4)") (class "Default")
      (node (ref "U2") (pin "4") (pinfunction "NC_4") (pintype "passive+no_connect"))
    )
    (net (code "116") (name "unconnected-(U2-NC-Pad5)") (class "Default")
      (node (ref "U2") (pin "5") (pinfunction "NC_5") (pintype "passive+no_connect"))
    )
    (net (code "117") (name "unconnected-(U3-Pad1)") (class "Default")
      (node (ref "U3") (pin "1") (pinfunction "1_1") (pintype "passive"))
    )
    (net (code "118") (name "unconnected-(U4A-PA8-Pad29)") (class "Default")
      (node (ref "U4") (pin "29") (pinfunction "PA8_29") (pintype "bidirectional"))
    )
    (net (code "119") (name "unconnected-(U4A-PA11-Pad32)") (class "Default")
      (node (ref "U4") (pin "32") (pinfunction "PA11_32") (pintype "bidirectional"))
    )
    (net (code "120") (name "unconnected-(U4A-PA12-Pad33)") (class "Default")
      (node (ref "U4") (pin "33") (pinfunction "PA12_33") (pintype "bidirectional"))
    )
    (net (code "121") (name "unconnected-(U4A-PA15-Pad38)") (class "Default")
      (node (ref "U4") (pin "38") (pinfunction "PA15_38") (pintype "bidirectional"))
    )
    (net (code "122") (name "unconnected-(U4A-PB2-Pad20)") (class "Default")
      (node (ref "U4") (pin "20") (pinfunction "PB2_20") (pintype "bidirectional"))
    )
    (net (code "123") (name "unconnected-(U4A-PB3-Pad39)") (class "Default")
      (node (ref "U4") (pin "39") (pinfunction "PB3_39") (pintype "bidirectional"))
    )
    (net (code "124") (name "unconnected-(U4A-PB4-Pad40)") (class "Default")
      (node (ref "U4") (pin "40") (pinfunction "PB4_40") (pintype "bidirectional"))
    )
    (net (code "125") (name "unconnected-(U4A-PB5-Pad41)") (class "Default")
      (node (ref "U4") (pin "41") (pinfunction "PB5_41") (pintype "bidirectional"))
    )
    (net (code "126") (name "unconnected-(U4A-PB6-Pad42)") (class "Default")
      (node (ref "U4") (pin "42") (pinfunction "PB6_42") (pintype "bidirectional"))
    )
    (net (code "127") (name "unconnected-(U4A-PB7-Pad43)") (class "Default")
      (node (ref "U4") (pin "43") (pinfunction "PB7_43") (pintype "bidirectional"))
    )
    (net (code "128") (name "unconnected-(U4A-PB12-Pad25)") (class "Default")
      (node (ref "U4") (pin "25") (pinfunction "PB12_25") (pintype "bidirectional"))
    )
    (net (code "129") (name "unconnected-(U4A-PB13-Pad26)") (class "Default")
      (node (ref "U4") (pin "26") (pinfunction "PB13_26") (pintype "bidirectional"))
    )
    (net (code "130") (name "unconnected-(U4A-PB14-Pad27)") (class "Default")
      (node (ref "U4") (pin "27") (pinfunction "PB14_27") (pintype "bidirectional"))
    )
    (net (code "131") (name "unconnected-(U4A-PB15-Pad28)") (class "Default")
      (node (ref "U4") (pin "28") (pinfunction "PB15_28") (pintype "bidirectional"))
    )
    (net (code "132") (name "unconnected-(U4A-PC14-OSC32_IN-Pad3)") (class "Default")
      (node (ref "U4") (pin "3") (pinfunction "PC14-OSC32_IN_3") (pintype "bidirectional"))
    )
    (net (code "133") (name "unconnected-(U4A-PC15-OSC32_OUT-Pad4)") (class "Default")
      (node (ref "U4") (pin "4") (pinfunction "PC15-OSC32_OUT_4") (pintype "bidirectional"))
    )
    (net (code "134") (name "unconnected-(U4A-PH0-OSC_IN-Pad5)") (class "Default")
      (node (ref "U4") (pin "5") (pinfunction "PH0-OSC_IN_5") (pintype "bidirectional"))
    )
    (net (code "135") (name "unconnected-(U4A-PH1-OSC_OUT-Pad6)") (class "Default")
      (node (ref "U4") (pin "6") (pinfunction "PH1-OSC_OUT_6") (pintype "bidirectional"))
    )
    (net (code "136") (name "unconnected-(U5-PG-Pad8)") (class "Default")
      (node (ref "U5") (pin "8") (pinfunction "PG_8") (pintype "passive"))
    )
    (net (code "137") (name "unconnected-(U8-GND-Pad4)") (class "Default")
      (node (ref "U8") (pin "4") (pinfunction "GND_4") (pintype "power_in"))
    )
  )
)
